# atmduinoboard.net
KiCad netlist of a schematic drawn in EAGLE
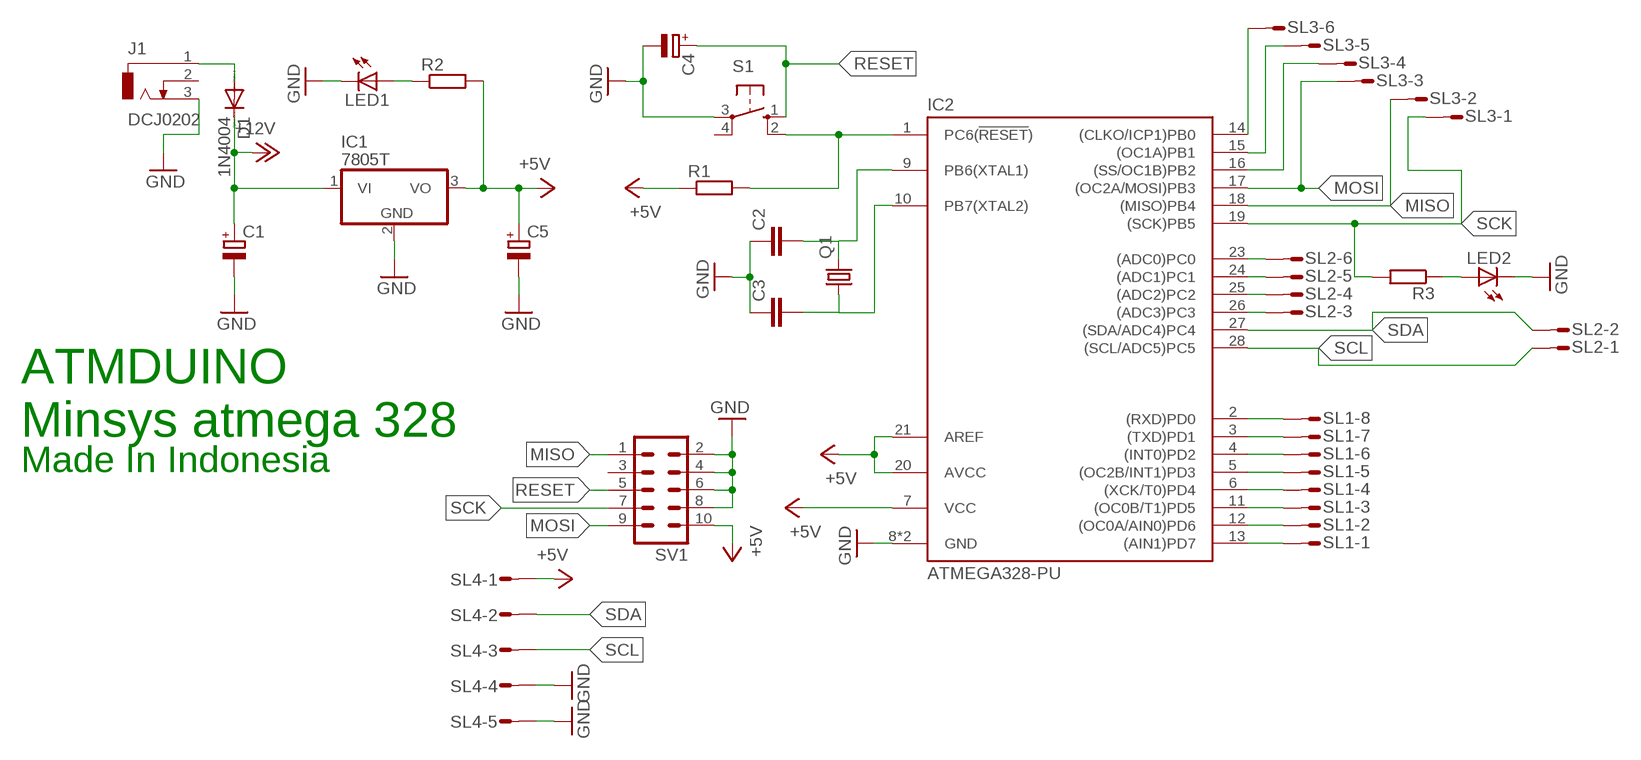
[diagram p0: schematic, sheet 1]

(export (version "E")
  (design (tool "Eeschema 10.0.6"))
  (components
    (comp (ref "C1")
      (value "CPOL-EUE2-4")
      (footprint "eagle-import:E2-4")
      (libsource (lib "eagle-import") (part "CPOL-EUE2-4"))
    )
    (comp (ref "C2")
      (value "C-EU025-024X044")
      (footprint "eagle-import:C025-024X044")
      (libsource (lib "eagle-import") (part "C-EU025-024X044"))
    )
    (comp (ref "C3")
      (value "C-EU025-024X044")
      (footprint "eagle-import:C025-024X044")
      (libsource (lib "eagle-import") (part "C-EU025-024X044"))
    )
    (comp (ref "C4")
      (value "CPOL-EUE2-4")
      (footprint "eagle-import:E2-4")
      (libsource (lib "eagle-import") (part "CPOL-EUE2-4"))
    )
    (comp (ref "C5")
      (value "CPOL-EUE2-4")
      (footprint "eagle-import:E2-4")
      (libsource (lib "eagle-import") (part "CPOL-EUE2-4"))
    )
    (comp (ref "D1")
      (value "1N4004")
      (footprint "eagle-import:DO41-10")
      (libsource (lib "eagle-import") (part "1N4004"))
    )
    (comp (ref "IC1")
      (value "7805T")
      (footprint "eagle-import:TO220H")
      (libsource (lib "eagle-import") (part "78T05"))
    )
    (comp (ref "IC2")
      (value "ATMEGA328-PU")
      (footprint "eagle-import:DIL28")
      (fields (field (name "MF") "Microchip"))
      (libsource (lib "eagle-import") (part "ATMEGA328-PU"))
    )
    (comp (ref "J1")
      (value "DCJ0202")
      (footprint "eagle-import:DCJ0202")
      (libsource (lib "eagle-import") (part "DCJ0202"))
    )
    (comp (ref "LED1")
      (value "LED3MM")
      (footprint "eagle-import:LED3MM")
      (libsource (lib "eagle-import") (part "LED3MM"))
    )
    (comp (ref "LED2")
      (value "LED3MM")
      (footprint "eagle-import:LED3MM")
      (libsource (lib "eagle-import") (part "LED3MM"))
    )
    (comp (ref "Q1")
      (value "CRYSTALHC49U-V")
      (footprint "eagle-import:HC49U-V")
      (libsource (lib "eagle-import") (part "CRYSTALHC49U-V"))
    )
    (comp (ref "R1")
      (value "R-EU_0204/5")
      (footprint "eagle-import:0204_5")
      (libsource (lib "eagle-import") (part "R-EU_0204/5"))
    )
    (comp (ref "R2")
      (value "R-EU_0204/5")
      (footprint "eagle-import:0204_5")
      (libsource (lib "eagle-import") (part "R-EU_0204/5"))
    )
    (comp (ref "R3")
      (value "R-EU_0204/5")
      (footprint "eagle-import:0204_5")
      (libsource (lib "eagle-import") (part "R-EU_0204/5"))
    )
    (comp (ref "S1")
      (value "10-XX")
      (footprint "eagle-import:B3F-10XX")
      (fields (field (name "MPN") "B3F-1000"))
      (libsource (lib "eagle-import") (part "10-XX"))
    )
    (comp (ref "SL1")
      (value "M08S")
      (footprint "eagle-import:08P")
      (libsource (lib "eagle-import") (part "M08S"))
    )
    (comp (ref "SL2")
      (value "M06S")
      (footprint "eagle-import:06P")
      (libsource (lib "eagle-import") (part "M06S"))
    )
    (comp (ref "SL3")
      (value "M06S")
      (footprint "eagle-import:06P")
      (libsource (lib "eagle-import") (part "M06S"))
    )
    (comp (ref "SL4")
      (value "M06S")
      (footprint "eagle-import:06P")
      (libsource (lib "eagle-import") (part "M06S"))
    )
    (comp (ref "SV1")
      (value "ML10")
      (footprint "eagle-import:ML10")
      (libsource (lib "eagle-import") (part "ML10"))
    )
  )
  (nets
    (net (code "1") (name "+5V") (class "Default")
      (node (ref "C5") (pin "+") (pinfunction "+_+") (pintype "passive"))
      (node (ref "IC1") (pin "3") (pinfunction "VO_3") (pintype "passive"))
      (node (ref "IC2") (pin "20") (pinfunction "AVCC_20") (pintype "power_in"))
      (node (ref "IC2") (pin "21") (pinfunction "AREF_21") (pintype "passive"))
      (node (ref "IC2") (pin "7") (pinfunction "VCC_7") (pintype "power_in"))
      (node (ref "R1") (pin "1") (pinfunction "1_1") (pintype "passive"))
      (node (ref "R2") (pin "2") (pinfunction "2_2") (pintype "passive"))
      (node (ref "SL4") (pin "1") (pinfunction "S_1") (pintype "passive"))
      (node (ref "SV1") (pin "10") (pinfunction "10_10") (pintype "passive"))
    )
    (net (code "2") (name "+12V") (class "Default")
      (node (ref "C1") (pin "+") (pinfunction "+_+") (pintype "passive"))
      (node (ref "D1") (pin "C") (pinfunction "C_C") (pintype "passive"))
      (node (ref "IC1") (pin "1") (pinfunction "VI_1") (pintype "input"))
    )
    (net (code "3") (name "GND") (class "Default")
      (node (ref "C1") (pin "-") (pinfunction "-_-") (pintype "passive"))
      (node (ref "C2") (pin "1") (pinfunction "1_1") (pintype "passive"))
      (node (ref "C3") (pin "1") (pinfunction "1_1") (pintype "passive"))
      (node (ref "C4") (pin "-") (pinfunction "-_-") (pintype "passive"))
      (node (ref "C5") (pin "-") (pinfunction "-_-") (pintype "passive"))
      (node (ref "IC1") (pin "2") (pinfunction "GND_2") (pintype "passive"))
      (node (ref "IC2") (pin "22") (pinfunction "GND_22") (pintype "power_in"))
      (node (ref "IC2") (pin "8") (pinfunction "GND_8") (pintype "power_in"))
      (node (ref "J1") (pin "3") (pinfunction "3_3") (pintype "passive"))
      (node (ref "LED1") (pin "K") (pinfunction "C_K") (pintype "passive"))
      (node (ref "LED2") (pin "K") (pinfunction "C_K") (pintype "passive"))
      (node (ref "S1") (pin "3") (pinfunction "P_3") (pintype "passive"))
      (node (ref "SL4") (pin "4") (pinfunction "S_4") (pintype "passive"))
      (node (ref "SL4") (pin "5") (pinfunction "S_5") (pintype "passive"))
      (node (ref "SV1") (pin "2") (pinfunction "2_2") (pintype "passive"))
      (node (ref "SV1") (pin "4") (pinfunction "4_4") (pintype "passive"))
      (node (ref "SV1") (pin "6") (pinfunction "6_6") (pintype "passive"))
      (node (ref "SV1") (pin "8") (pinfunction "8_8") (pintype "passive"))
    )
    (net (code "4") (name "MISO") (class "Default")
      (node (ref "IC2") (pin "18") (pinfunction "(MISO)PB4_18") (pintype "bidirectional"))
      (node (ref "SL3") (pin "2") (pinfunction "S_2") (pintype "passive"))
      (node (ref "SV1") (pin "1") (pinfunction "1_1") (pintype "passive"))
    )
    (net (code "5") (name "MOSI") (class "Default")
      (node (ref "IC2") (pin "17") (pinfunction "(OC2A/MOSI)PB3_17") (pintype "bidirectional"))
      (node (ref "SL3") (pin "3") (pinfunction "S_3") (pintype "passive"))
      (node (ref "SV1") (pin "9") (pinfunction "9_9") (pintype "passive"))
    )
    (net (code "6") (name "Net-(D1-PadA)") (class "Default")
      (node (ref "D1") (pin "A") (pinfunction "A_A") (pintype "passive"))
      (node (ref "J1") (pin "1") (pinfunction "1_1") (pintype "passive"))
    )
    (net (code "7") (name "Net-(IC2-(ADC0)PC0)") (class "Default")
      (node (ref "IC2") (pin "23") (pinfunction "(ADC0)PC0_23") (pintype "bidirectional"))
      (node (ref "SL2") (pin "6") (pinfunction "S_6") (pintype "passive"))
    )
    (net (code "8") (name "Net-(IC2-(ADC1)PC1)") (class "Default")
      (node (ref "IC2") (pin "24") (pinfunction "(ADC1)PC1_24") (pintype "bidirectional"))
      (node (ref "SL2") (pin "5") (pinfunction "S_5") (pintype "passive"))
    )
    (net (code "9") (name "Net-(IC2-(ADC2)PC2)") (class "Default")
      (node (ref "IC2") (pin "25") (pinfunction "(ADC2)PC2_25") (pintype "bidirectional"))
      (node (ref "SL2") (pin "4") (pinfunction "S_4") (pintype "passive"))
    )
    (net (code "10") (name "Net-(IC2-(ADC3)PC3)") (class "Default")
      (node (ref "IC2") (pin "26") (pinfunction "(ADC3)PC3_26") (pintype "bidirectional"))
      (node (ref "SL2") (pin "3") (pinfunction "S_3") (pintype "passive"))
    )
    (net (code "11") (name "Net-(IC2-(AIN1)PD7)") (class "Default")
      (node (ref "IC2") (pin "13") (pinfunction "(AIN1)PD7_13") (pintype "bidirectional"))
      (node (ref "SL1") (pin "1") (pinfunction "S_1") (pintype "passive"))
    )
    (net (code "12") (name "Net-(IC2-(CLKO{slash}ICP1)PB0)") (class "Default")
      (node (ref "IC2") (pin "14") (pinfunction "(CLKO/ICP1)PB0_14") (pintype "bidirectional"))
      (node (ref "SL3") (pin "6") (pinfunction "S_6") (pintype "passive"))
    )
    (net (code "13") (name "Net-(IC2-(INT0)PD2)") (class "Default")
      (node (ref "IC2") (pin "4") (pinfunction "(INT0)PD2_4") (pintype "bidirectional"))
      (node (ref "SL1") (pin "6") (pinfunction "S_6") (pintype "passive"))
    )
    (net (code "14") (name "Net-(IC2-(OC0A{slash}AIN0)PD6)") (class "Default")
      (node (ref "IC2") (pin "12") (pinfunction "(OC0A/AIN0)PD6_12") (pintype "bidirectional"))
      (node (ref "SL1") (pin "2") (pinfunction "S_2") (pintype "passive"))
    )
    (net (code "15") (name "Net-(IC2-(OC0B{slash}T1)PD5)") (class "Default")
      (node (ref "IC2") (pin "11") (pinfunction "(OC0B/T1)PD5_11") (pintype "bidirectional"))
      (node (ref "SL1") (pin "3") (pinfunction "S_3") (pintype "passive"))
    )
    (net (code "16") (name "Net-(IC2-(OC1A)PB1)") (class "Default")
      (node (ref "IC2") (pin "15") (pinfunction "(OC1A)PB1_15") (pintype "bidirectional"))
      (node (ref "SL3") (pin "5") (pinfunction "S_5") (pintype "passive"))
    )
    (net (code "17") (name "Net-(IC2-(OC2B{slash}INT1)PD3)") (class "Default")
      (node (ref "IC2") (pin "5") (pinfunction "(OC2B/INT1)PD3_5") (pintype "bidirectional"))
      (node (ref "SL1") (pin "5") (pinfunction "S_5") (pintype "passive"))
    )
    (net (code "18") (name "Net-(IC2-(RXD)PD0)") (class "Default")
      (node (ref "IC2") (pin "2") (pinfunction "(RXD)PD0_2") (pintype "bidirectional"))
      (node (ref "SL1") (pin "8") (pinfunction "S_8") (pintype "passive"))
    )
    (net (code "19") (name "Net-(IC2-(SS{slash}OC1B)PB2)") (class "Default")
      (node (ref "IC2") (pin "16") (pinfunction "(SS/OC1B)PB2_16") (pintype "bidirectional"))
      (node (ref "SL3") (pin "4") (pinfunction "S_4") (pintype "passive"))
    )
    (net (code "20") (name "Net-(IC2-(TXD)PD1)") (class "Default")
      (node (ref "IC2") (pin "3") (pinfunction "(TXD)PD1_3") (pintype "bidirectional"))
      (node (ref "SL1") (pin "7") (pinfunction "S_7") (pintype "passive"))
    )
    (net (code "21") (name "Net-(IC2-(XCK{slash}T0)PD4)") (class "Default")
      (node (ref "IC2") (pin "6") (pinfunction "(XCK/T0)PD4_6") (pintype "bidirectional"))
      (node (ref "SL1") (pin "4") (pinfunction "S_4") (pintype "passive"))
    )
    (net (code "22") (name "Net-(IC2-PB6(XTAL1))") (class "Default")
      (node (ref "C2") (pin "2") (pinfunction "2_2") (pintype "passive"))
      (node (ref "IC2") (pin "9") (pinfunction "PB6(XTAL1)_9") (pintype "bidirectional"))
      (node (ref "Q1") (pin "2") (pinfunction "2_2") (pintype "passive"))
    )
    (net (code "23") (name "Net-(IC2-PB7(XTAL2))") (class "Default")
      (node (ref "C3") (pin "2") (pinfunction "2_2") (pintype "passive"))
      (node (ref "IC2") (pin "10") (pinfunction "PB7(XTAL2)_10") (pintype "bidirectional"))
      (node (ref "Q1") (pin "1") (pinfunction "1_1") (pintype "passive"))
    )
    (net (code "24") (name "Net-(IC2-PC6(~{RESET}))") (class "Default")
      (node (ref "IC2") (pin "1") (pinfunction "PC6(~{RESET})_1") (pintype "bidirectional"))
      (node (ref "R1") (pin "2") (pinfunction "2_2") (pintype "passive"))
      (node (ref "S1") (pin "2") (pinfunction "S1_2") (pintype "passive"))
    )
    (net (code "25") (name "Net-(LED1-PadA)") (class "Default")
      (node (ref "LED1") (pin "A") (pinfunction "A_A") (pintype "passive"))
      (node (ref "R2") (pin "1") (pinfunction "1_1") (pintype "passive"))
    )
    (net (code "26") (name "Net-(LED2-PadA)") (class "Default")
      (node (ref "LED2") (pin "A") (pinfunction "A_A") (pintype "passive"))
      (node (ref "R3") (pin "1") (pinfunction "1_1") (pintype "passive"))
    )
    (net (code "27") (name "RESET") (class "Default")
      (node (ref "C4") (pin "+") (pinfunction "+_+") (pintype "passive"))
      (node (ref "S1") (pin "1") (pinfunction "S_1") (pintype "passive"))
      (node (ref "SV1") (pin "5") (pinfunction "5_5") (pintype "passive"))
    )
    (net (code "28") (name "SCK") (class "Default")
      (node (ref "IC2") (pin "19") (pinfunction "(SCK)PB5_19") (pintype "bidirectional"))
      (node (ref "R3") (pin "2") (pinfunction "2_2") (pintype "passive"))
      (node (ref "SL3") (pin "1") (pinfunction "S_1") (pintype "passive"))
      (node (ref "SV1") (pin "7") (pinfunction "7_7") (pintype "passive"))
    )
    (net (code "29") (name "SCL") (class "Default")
      (node (ref "IC2") (pin "28") (pinfunction "(SCL/ADC5)PC5_28") (pintype "bidirectional"))
      (node (ref "SL2") (pin "1") (pinfunction "S_1") (pintype "passive"))
      (node (ref "SL4") (pin "3") (pinfunction "S_3") (pintype "passive"))
    )
    (net (code "30") (name "SDA") (class "Default")
      (node (ref "IC2") (pin "27") (pinfunction "(SDA/ADC4)PC4_27") (pintype "bidirectional"))
      (node (ref "SL2") (pin "2") (pinfunction "S_2") (pintype "passive"))
      (node (ref "SL4") (pin "2") (pinfunction "S_2") (pintype "passive"))
    )
    (net (code "31") (name "unconnected-(J1-Pad2)") (class "Default")
      (node (ref "J1") (pin "2") (pinfunction "2_2") (pintype "passive"))
    )
    (net (code "32") (name "unconnected-(S1-P1-Pad4)") (class "Default")
      (node (ref "S1") (pin "4") (pinfunction "P1_4") (pintype "passive"))
    )
    (net (code "33") (name "unconnected-(SV1-Pad3)") (class "Default")
      (node (ref "SV1") (pin "3") (pinfunction "3_3") (pintype "passive"))
    )
  )
)
